# main.net
KiCad netlist of a schematic drawn in Altium Designer
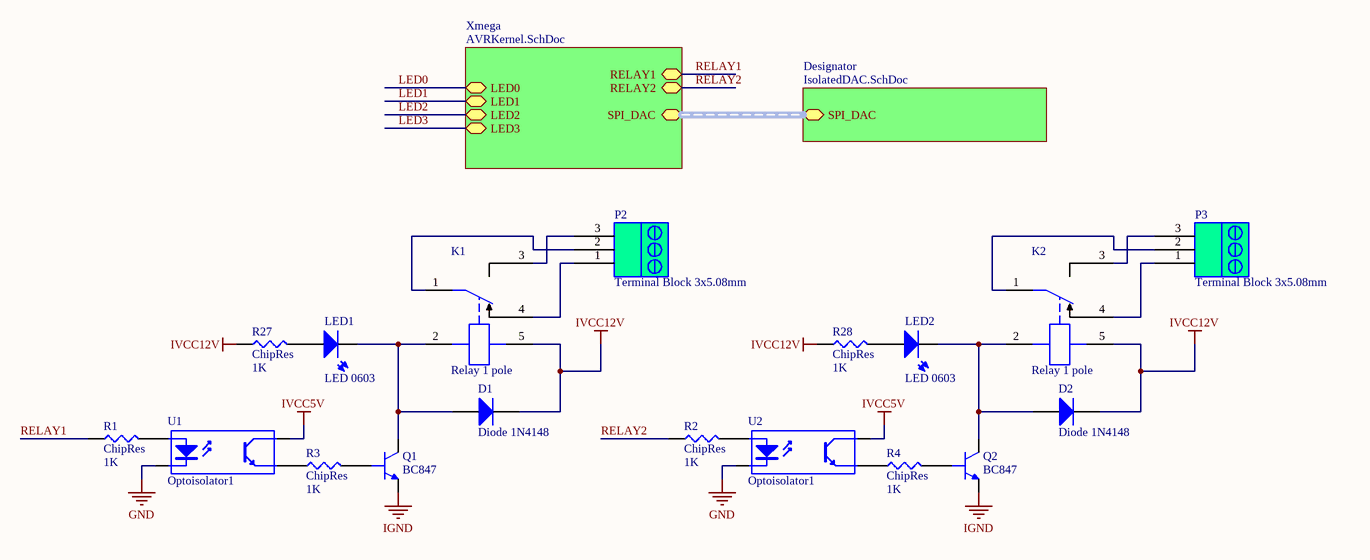
[diagram p0: main.SchDoc]

(export (version "E")
  (design (tool "Eeschema 10.0.6"))
  (components
    (comp (ref "D1")
      (value "Diode 1N4148")
      (footprint "DO-35")
      (description "High Conductance Fast Diode")
      (fields (field (name "PUBLISHER") "Altium Limited"))
      (libsource (lib "Miscellaneous Devices") (part "Diode 1N4148"))
    )
    (comp (ref "D2")
      (value "Diode 1N4148")
      (footprint "DO-35")
      (description "High Conductance Fast Diode")
      (fields (field (name "PUBLISHER") "Altium Limited"))
      (libsource (lib "Miscellaneous Devices") (part "Diode 1N4148"))
    )
    (comp (ref "K1")
      (value "Relay 1 pole")
      (footprint "G5LA")
      (description "Relay G5LE 10A Single Pole")
      (libsource (lib "OMRON Relay") (part "Relay G5LE"))
    )
    (comp (ref "K2")
      (value "Relay 1 pole")
      (footprint "G5LA")
      (description "Relay G5LE 10A Single Pole")
      (libsource (lib "OMRON Relay") (part "Relay G5LE"))
    )
    (comp (ref "LED1") (value "LED 0603") (footprint "LED 0603") (libsource (lib "LEDs") (part "LED0603")))
    (comp (ref "LED2") (value "LED 0603") (footprint "LED 0603") (libsource (lib "LEDs") (part "LED0603")))
    (comp (ref "P2")
      (value "Terminal Block 3x5.08mm")
      (footprint "Socket 3x5.08")
      (description "Terminal Block Socket Right Angle 3x5.08mm 2-Wall")
      (libsource (lib "IndustrialConnectors") (part "Socket_3x5.08_RA_2Wall"))
    )
    (comp (ref "P3")
      (value "Terminal Block 3x5.08mm")
      (footprint "Socket 3x5.08")
      (description "Terminal Block Socket Right Angle 3x5.08mm 2-Wall")
      (libsource (lib "IndustrialConnectors") (part "Socket_3x5.08_RA_2Wall"))
    )
    (comp (ref "Q1")
      (value "BC847")
      (footprint "SOT23")
      (description "NPN transistor")
      (libsource (lib "BJT") (part "BC847"))
    )
    (comp (ref "Q2")
      (value "BC847")
      (footprint "SOT23")
      (description "NPN transistor")
      (libsource (lib "BJT") (part "BC847"))
    )
    (comp (ref "R1")
      (value "ChipRes")
      (footprint "RES0805")
      (description "Chip resistor")
      (fields (field (name "ALTIUM_VALUE") "1K"))
      (libsource (lib "Common Devices") (part "ChipRes"))
    )
    (comp (ref "R2")
      (value "ChipRes")
      (footprint "RES0805")
      (description "Chip resistor")
      (fields (field (name "ALTIUM_VALUE") "1K"))
      (libsource (lib "Common Devices") (part "ChipRes"))
    )
    (comp (ref "R3")
      (value "ChipRes")
      (footprint "RES0805")
      (description "Chip resistor")
      (fields (field (name "ALTIUM_VALUE") "1K"))
      (libsource (lib "Common Devices") (part "ChipRes"))
    )
    (comp (ref "R4")
      (value "ChipRes")
      (footprint "RES0805")
      (description "Chip resistor")
      (fields (field (name "ALTIUM_VALUE") "1K"))
      (libsource (lib "Common Devices") (part "ChipRes"))
    )
    (comp (ref "R27")
      (value "ChipRes")
      (footprint "RES0805")
      (description "Chip resistor")
      (fields (field (name "ALTIUM_VALUE") "1K"))
      (libsource (lib "Common Devices") (part "ChipRes"))
    )
    (comp (ref "R28")
      (value "ChipRes")
      (footprint "RES0805")
      (description "Chip resistor")
      (fields (field (name "ALTIUM_VALUE") "1K"))
      (libsource (lib "Common Devices") (part "ChipRes"))
    )
    (comp (ref "U1")
      (value "Optoisolator1")
      (footprint "DIP-4")
      (description "4-Pin Phototransistor Optocoupler")
      (fields (field (name "PUBLISHER") "Altium Limited"))
      (libsource (lib "Miscellaneous Devices") (part "Optoisolator1"))
    )
    (comp (ref "U2")
      (value "Optoisolator1")
      (footprint "DIP-4")
      (description "4-Pin Phototransistor Optocoupler")
      (fields (field (name "PUBLISHER") "Altium Limited"))
      (libsource (lib "Miscellaneous Devices") (part "Optoisolator1"))
    )
  )
  (nets
    (net (code "5") (name "/RELAY1") (class "Default") (node (ref "R1") (pin "1") (pintype "passive")))
    (net (code "6") (name "/RELAY2") (class "Default") (node (ref "R2") (pin "1") (pintype "passive")))
    (net (code "8") (name "GND") (class "Default")
      (node (ref "U1") (pin "2") (pinfunction "K_2") (pintype "passive"))
      (node (ref "U2") (pin "2") (pinfunction "K_2") (pintype "passive"))
    )
    (net (code "9") (name "IGND") (class "Default")
      (node (ref "Q1") (pin "2") (pinfunction "2_2") (pintype "passive"))
      (node (ref "Q2") (pin "2") (pinfunction "2_2") (pintype "passive"))
    )
    (net (code "10") (name "IVCC5V") (class "Default")
      (node (ref "U1") (pin "4") (pinfunction "C_4") (pintype "passive"))
      (node (ref "U2") (pin "4") (pinfunction "C_4") (pintype "passive"))
    )
    (net (code "11") (name "IVCC12V") (class "Default")
      (node (ref "D1") (pin "2") (pinfunction "K_2") (pintype "passive"))
      (node (ref "D2") (pin "2") (pinfunction "K_2") (pintype "passive"))
      (node (ref "K1") (pin "5") (pinfunction "5_5") (pintype "passive"))
      (node (ref "K2") (pin "5") (pinfunction "5_5") (pintype "passive"))
      (node (ref "R27") (pin "1") (pintype "passive"))
      (node (ref "R28") (pin "1") (pintype "passive"))
    )
    (net (code "12") (name "Net-(D1-A)") (class "Default")
      (node (ref "D1") (pin "1") (pinfunction "A_1") (pintype "passive"))
      (node (ref "K1") (pin "2") (pinfunction "2_2") (pintype "passive"))
      (node (ref "LED1") (pin "1") (pinfunction "1_1") (pintype "passive"))
      (node (ref "Q1") (pin "3") (pinfunction "3_3") (pintype "passive"))
    )
    (net (code "13") (name "Net-(D2-A)") (class "Default")
      (node (ref "D2") (pin "1") (pinfunction "A_1") (pintype "passive"))
      (node (ref "K2") (pin "2") (pinfunction "2_2") (pintype "passive"))
      (node (ref "LED2") (pin "1") (pinfunction "1_1") (pintype "passive"))
      (node (ref "Q2") (pin "3") (pinfunction "3_3") (pintype "passive"))
    )
    (net (code "14") (name "Net-(K1-Pad1)") (class "Default")
      (node (ref "K1") (pin "1") (pinfunction "1_1") (pintype "passive"))
      (node (ref "P2") (pin "2") (pintype "passive"))
    )
    (net (code "15") (name "Net-(K1-Pad3)") (class "Default")
      (node (ref "K1") (pin "3") (pinfunction "3_3") (pintype "passive"))
      (node (ref "P2") (pin "3") (pintype "passive"))
    )
    (net (code "16") (name "Net-(K1-Pad4)") (class "Default")
      (node (ref "K1") (pin "4") (pinfunction "4_4") (pintype "passive"))
      (node (ref "P2") (pin "1") (pintype "passive"))
    )
    (net (code "17") (name "Net-(K2-Pad1)") (class "Default")
      (node (ref "K2") (pin "1") (pinfunction "1_1") (pintype "passive"))
      (node (ref "P3") (pin "2") (pintype "passive"))
    )
    (net (code "18") (name "Net-(K2-Pad3)") (class "Default")
      (node (ref "K2") (pin "3") (pinfunction "3_3") (pintype "passive"))
      (node (ref "P3") (pin "3") (pintype "passive"))
    )
    (net (code "19") (name "Net-(K2-Pad4)") (class "Default")
      (node (ref "K2") (pin "4") (pinfunction "4_4") (pintype "passive"))
      (node (ref "P3") (pin "1") (pintype "passive"))
    )
    (net (code "20") (name "Net-(LED1-Pad2)") (class "Default")
      (node (ref "LED1") (pin "2") (pinfunction "2_2") (pintype "passive"))
      (node (ref "R27") (pin "2") (pintype "passive"))
    )
    (net (code "21") (name "Net-(LED2-Pad2)") (class "Default")
      (node (ref "LED2") (pin "2") (pinfunction "2_2") (pintype "passive"))
      (node (ref "R28") (pin "2") (pintype "passive"))
    )
    (net (code "22") (name "Net-(Q1-Pad1)") (class "Default")
      (node (ref "Q1") (pin "1") (pinfunction "1_1") (pintype "passive"))
      (node (ref "R3") (pin "2") (pintype "passive"))
    )
    (net (code "23") (name "Net-(Q2-Pad1)") (class "Default")
      (node (ref "Q2") (pin "1") (pinfunction "1_1") (pintype "passive"))
      (node (ref "R4") (pin "2") (pintype "passive"))
    )
    (net (code "24") (name "Net-(U1-A)") (class "Default")
      (node (ref "R1") (pin "2") (pintype "passive"))
      (node (ref "U1") (pin "1") (pinfunction "A_1") (pintype "passive"))
    )
    (net (code "25") (name "Net-(U1-E)") (class "Default")
      (node (ref "R3") (pin "1") (pintype "passive"))
      (node (ref "U1") (pin "3") (pinfunction "E_3") (pintype "passive"))
    )
    (net (code "26") (name "Net-(U2-A)") (class "Default")
      (node (ref "R2") (pin "2") (pintype "passive"))
      (node (ref "U2") (pin "1") (pinfunction "A_1") (pintype "passive"))
    )
    (net (code "27") (name "Net-(U2-E)") (class "Default")
      (node (ref "R4") (pin "1") (pintype "passive"))
      (node (ref "U2") (pin "3") (pinfunction "E_3") (pintype "passive"))
    )
  )
)
